# TSMPC.net
KiCad netlist of a schematic drawn in EAGLE
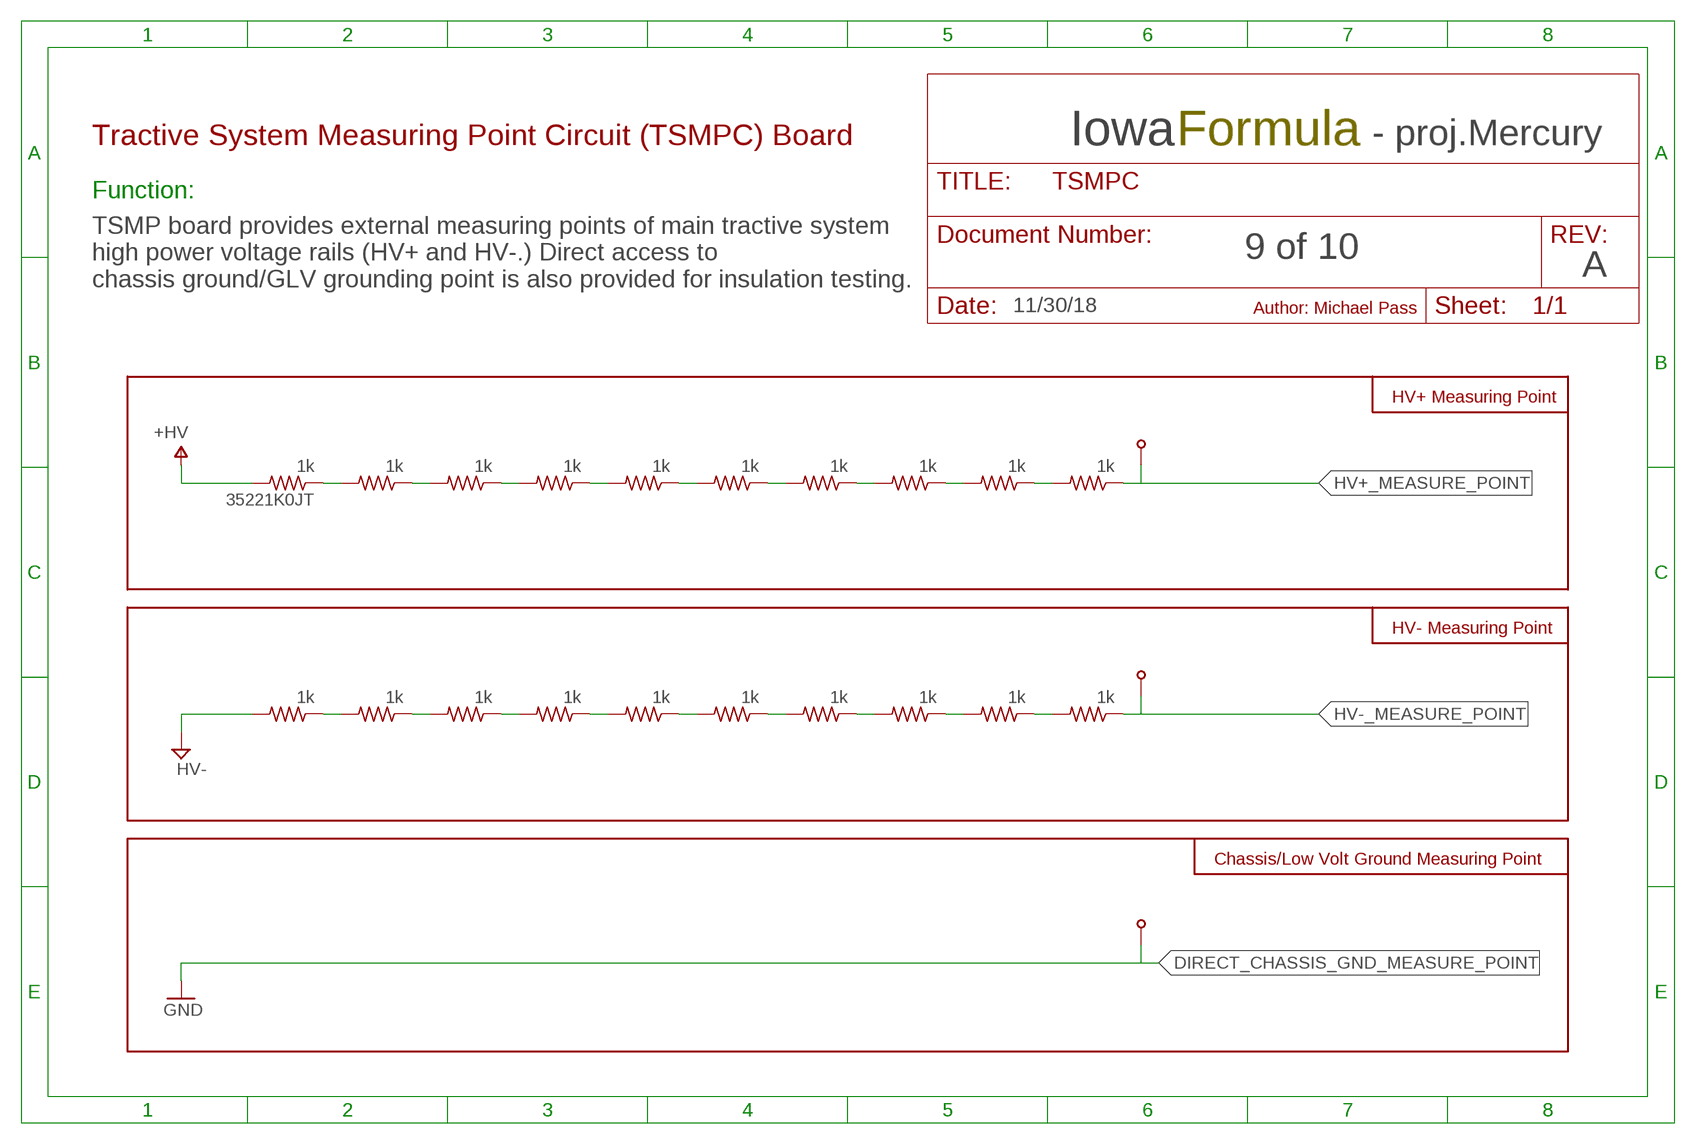
[diagram p0: schematic, sheet 1]

(export (version "E")
  (design (tool "Eeschema 10.0.6"))
  (components
    (comp (ref "35221K0JT")
      (value "1k")
      (footprint "eagle-import:R0805")
      (libsource (lib "eagle-import") (part "R-US_R0805"))
    )
    (comp (ref "R2")
      (value "1k")
      (footprint "eagle-import:R0805")
      (libsource (lib "eagle-import") (part "R-US_R0805"))
    )
    (comp (ref "R3")
      (value "1k")
      (footprint "eagle-import:R0805")
      (libsource (lib "eagle-import") (part "R-US_R0805"))
    )
    (comp (ref "R4")
      (value "1k")
      (footprint "eagle-import:R0805")
      (libsource (lib "eagle-import") (part "R-US_R0805"))
    )
    (comp (ref "R5")
      (value "1k")
      (footprint "eagle-import:R0805")
      (libsource (lib "eagle-import") (part "R-US_R0805"))
    )
    (comp (ref "R6")
      (value "1k")
      (footprint "eagle-import:R0805")
      (libsource (lib "eagle-import") (part "R-US_R0805"))
    )
    (comp (ref "R7")
      (value "1k")
      (footprint "eagle-import:R0805")
      (libsource (lib "eagle-import") (part "R-US_R0805"))
    )
    (comp (ref "R8")
      (value "1k")
      (footprint "eagle-import:R0805")
      (libsource (lib "eagle-import") (part "R-US_R0805"))
    )
    (comp (ref "R9")
      (value "1k")
      (footprint "eagle-import:R0805")
      (libsource (lib "eagle-import") (part "R-US_R0805"))
    )
    (comp (ref "R10")
      (value "1k")
      (footprint "eagle-import:R0805")
      (libsource (lib "eagle-import") (part "R-US_R0805"))
    )
    (comp (ref "R21")
      (value "1k")
      (footprint "eagle-import:R0805")
      (libsource (lib "eagle-import") (part "R-US_R0805"))
    )
    (comp (ref "R22")
      (value "1k")
      (footprint "eagle-import:R0805")
      (libsource (lib "eagle-import") (part "R-US_R0805"))
    )
    (comp (ref "R23")
      (value "1k")
      (footprint "eagle-import:R0805")
      (libsource (lib "eagle-import") (part "R-US_R0805"))
    )
    (comp (ref "R24")
      (value "1k")
      (footprint "eagle-import:R0805")
      (libsource (lib "eagle-import") (part "R-US_R0805"))
    )
    (comp (ref "R25")
      (value "1k")
      (footprint "eagle-import:R0805")
      (libsource (lib "eagle-import") (part "R-US_R0805"))
    )
    (comp (ref "R26")
      (value "1k")
      (footprint "eagle-import:R0805")
      (libsource (lib "eagle-import") (part "R-US_R0805"))
    )
    (comp (ref "R27")
      (value "1k")
      (footprint "eagle-import:R0805")
      (libsource (lib "eagle-import") (part "R-US_R0805"))
    )
    (comp (ref "R28")
      (value "1k")
      (footprint "eagle-import:R0805")
      (libsource (lib "eagle-import") (part "R-US_R0805"))
    )
    (comp (ref "R29")
      (value "1k")
      (footprint "eagle-import:R0805")
      (libsource (lib "eagle-import") (part "R-US_R0805"))
    )
    (comp (ref "R30")
      (value "1k")
      (footprint "eagle-import:R0805")
      (libsource (lib "eagle-import") (part "R-US_R0805"))
    )
    (comp (ref "U$1")
      (value "BANANA-JACK")
      (footprint "eagle-import:BANANA-PRINT")
      (libsource (lib "eagle-import") (part "BANANA-JACK"))
    )
    (comp (ref "U$3")
      (value "BANANA-JACK")
      (footprint "eagle-import:BANANA-PRINT")
      (libsource (lib "eagle-import") (part "BANANA-JACK"))
    )
    (comp (ref "U$4")
      (value "BANANA-JACK")
      (footprint "eagle-import:BANANA-PRINT")
      (libsource (lib "eagle-import") (part "BANANA-JACK"))
    )
  )
  (nets
    (net (code "1") (name "+HV") (class "Default")
      (node (ref "35221K0JT") (pin "2") (pinfunction "2_2") (pintype "passive"))
    )
    (net (code "2") (name "DIRECT_CHASSIS_GND_MEASURE_POINT") (class "Default")
      (node (ref "R21") (pin "2") (pinfunction "2_2") (pintype "passive"))
      (node (ref "U$3") (pin "P$1") (pinfunction "PIN_P$1") (pintype "bidirectional"))
    )
    (net (code "3") (name "HV+_MEASURE_POINT") (class "Default")
      (node (ref "R10") (pin "1") (pinfunction "1_1") (pintype "passive"))
      (node (ref "U$1") (pin "P$1") (pinfunction "PIN_P$1") (pintype "bidirectional"))
    )
    (net (code "4") (name "HV-_MEASURE_POINT") (class "Default")
      (node (ref "R30") (pin "1") (pinfunction "1_1") (pintype "passive"))
      (node (ref "U$4") (pin "P$1") (pinfunction "PIN_P$1") (pintype "bidirectional"))
    )
    (net (code "5") (name "Net-(35221K0JT-Pad1)") (class "Default")
      (node (ref "35221K0JT") (pin "1") (pinfunction "1_1") (pintype "passive"))
      (node (ref "R2") (pin "2") (pinfunction "2_2") (pintype "passive"))
    )
    (net (code "6") (name "Net-(R2-Pad1)") (class "Default")
      (node (ref "R2") (pin "1") (pinfunction "1_1") (pintype "passive"))
      (node (ref "R3") (pin "2") (pinfunction "2_2") (pintype "passive"))
    )
    (net (code "7") (name "Net-(R3-Pad1)") (class "Default")
      (node (ref "R3") (pin "1") (pinfunction "1_1") (pintype "passive"))
      (node (ref "R4") (pin "2") (pinfunction "2_2") (pintype "passive"))
    )
    (net (code "8") (name "Net-(R4-Pad1)") (class "Default")
      (node (ref "R4") (pin "1") (pinfunction "1_1") (pintype "passive"))
      (node (ref "R5") (pin "2") (pinfunction "2_2") (pintype "passive"))
    )
    (net (code "9") (name "Net-(R5-Pad1)") (class "Default")
      (node (ref "R5") (pin "1") (pinfunction "1_1") (pintype "passive"))
      (node (ref "R6") (pin "2") (pinfunction "2_2") (pintype "passive"))
    )
    (net (code "10") (name "Net-(R6-Pad1)") (class "Default")
      (node (ref "R6") (pin "1") (pinfunction "1_1") (pintype "passive"))
      (node (ref "R7") (pin "2") (pinfunction "2_2") (pintype "passive"))
    )
    (net (code "11") (name "Net-(R7-Pad1)") (class "Default")
      (node (ref "R7") (pin "1") (pinfunction "1_1") (pintype "passive"))
      (node (ref "R8") (pin "2") (pinfunction "2_2") (pintype "passive"))
    )
    (net (code "12") (name "Net-(R8-Pad1)") (class "Default")
      (node (ref "R8") (pin "1") (pinfunction "1_1") (pintype "passive"))
      (node (ref "R9") (pin "2") (pinfunction "2_2") (pintype "passive"))
    )
    (net (code "13") (name "Net-(R10-Pad2)") (class "Default")
      (node (ref "R10") (pin "2") (pinfunction "2_2") (pintype "passive"))
      (node (ref "R9") (pin "1") (pinfunction "1_1") (pintype "passive"))
    )
    (net (code "14") (name "Net-(R21-Pad1)") (class "Default")
      (node (ref "R21") (pin "1") (pinfunction "1_1") (pintype "passive"))
      (node (ref "R22") (pin "2") (pinfunction "2_2") (pintype "passive"))
    )
    (net (code "15") (name "Net-(R22-Pad1)") (class "Default")
      (node (ref "R22") (pin "1") (pinfunction "1_1") (pintype "passive"))
      (node (ref "R23") (pin "2") (pinfunction "2_2") (pintype "passive"))
    )
    (net (code "16") (name "Net-(R23-Pad1)") (class "Default")
      (node (ref "R23") (pin "1") (pinfunction "1_1") (pintype "passive"))
      (node (ref "R24") (pin "2") (pinfunction "2_2") (pintype "passive"))
    )
    (net (code "17") (name "Net-(R24-Pad1)") (class "Default")
      (node (ref "R24") (pin "1") (pinfunction "1_1") (pintype "passive"))
      (node (ref "R25") (pin "2") (pinfunction "2_2") (pintype "passive"))
    )
    (net (code "18") (name "Net-(R25-Pad1)") (class "Default")
      (node (ref "R25") (pin "1") (pinfunction "1_1") (pintype "passive"))
      (node (ref "R26") (pin "2") (pinfunction "2_2") (pintype "passive"))
    )
    (net (code "19") (name "Net-(R26-Pad1)") (class "Default")
      (node (ref "R26") (pin "1") (pinfunction "1_1") (pintype "passive"))
      (node (ref "R27") (pin "2") (pinfunction "2_2") (pintype "passive"))
    )
    (net (code "20") (name "Net-(R27-Pad1)") (class "Default")
      (node (ref "R27") (pin "1") (pinfunction "1_1") (pintype "passive"))
      (node (ref "R28") (pin "2") (pinfunction "2_2") (pintype "passive"))
    )
    (net (code "21") (name "Net-(R28-Pad1)") (class "Default")
      (node (ref "R28") (pin "1") (pinfunction "1_1") (pintype "passive"))
      (node (ref "R29") (pin "2") (pinfunction "2_2") (pintype "passive"))
    )
    (net (code "22") (name "Net-(R29-Pad1)") (class "Default")
      (node (ref "R29") (pin "1") (pinfunction "1_1") (pintype "passive"))
      (node (ref "R30") (pin "2") (pinfunction "2_2") (pintype "passive"))
    )
  )
)
